# TLM_002_ESP32S3.net
KiCad netlist of a schematic drawn in Altium Designer
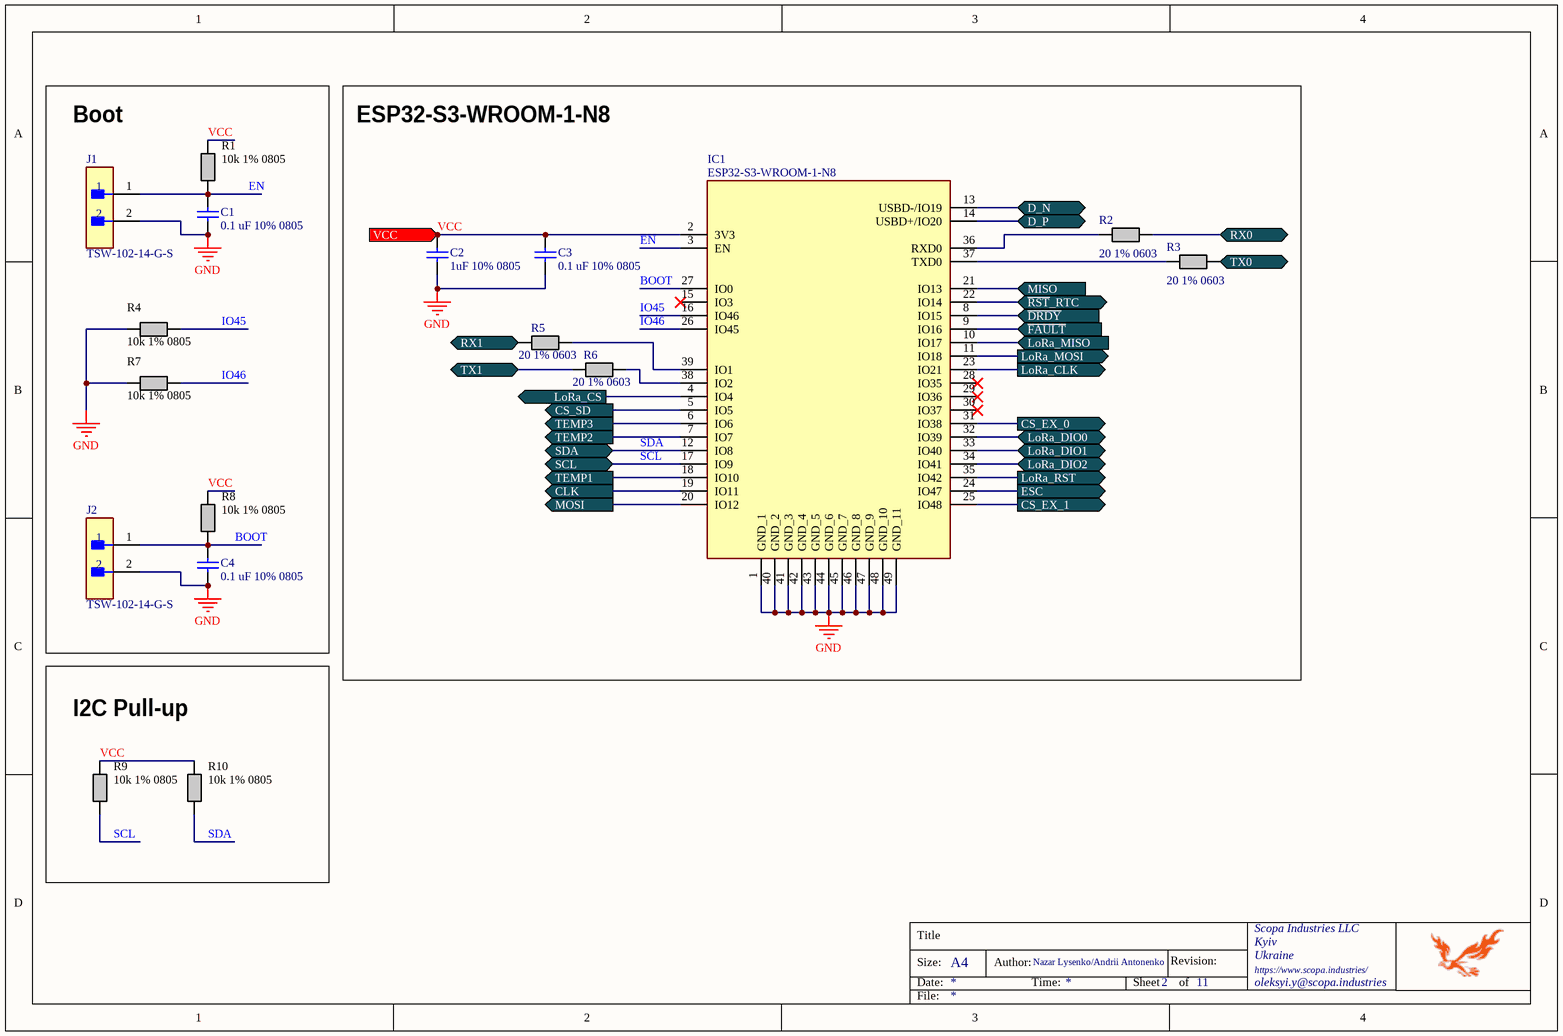
[diagram p0: TLM_002_ESP32S3.SchDoc]

(export (version "E")
  (design (tool "Eeschema 10.0.6"))
  (components
    (comp (ref "C1")
      (value "0.1 uF 10% 0805")
      (footprint "CAPC2013X140X50ML20T25")
      (fields
        (field (name "PART NUMBER") "0805DD104KAT2A")
        (field (name "MANUFACTURER") "AVX Interconnect / Elco")
      )
      (libsource (lib "Altium Content Vault") (part "CAP"))
    )
    (comp (ref "C2")
      (value "1uF 10% 0805")
      (footprint "CAPC2013X145X50NL20T20")
      (fields (field (name "PART NUMBER") "VJ0805Y105KXQRW1BC") (field (name "MANUFACTURER") "Vitramon"))
      (libsource (lib "Altium Content Vault") (part "CAP"))
    )
    (comp (ref "C3")
      (value "0.1 uF 10% 0805")
      (footprint "CAPC2013X140X50ML20T25")
      (fields
        (field (name "PART NUMBER") "0805DD104KAT2A")
        (field (name "MANUFACTURER") "AVX Interconnect / Elco")
      )
      (libsource (lib "Altium Content Vault") (part "CAP"))
    )
    (comp (ref "C4")
      (value "0.1 uF 10% 0805")
      (footprint "CAPC2013X140X50ML20T25")
      (fields
        (field (name "PART NUMBER") "0805DD104KAT2A")
        (field (name "MANUFACTURER") "AVX Interconnect / Elco")
      )
      (libsource (lib "Altium Content Vault") (part "CAP"))
    )
    (comp (ref "IC1")
      (value "ESP32-S3-WROOM-1-N8")
      (footprint "SamacSys:ESP32S3WROOM1N8R2")
      (description "Integrated Circuit")
      (fields (field (name "MOUSER PART NUMBER") "356-ESP32-S3WROOM1N8"))
      (libsource (lib "SamacSys") (part "ESP32-S3-WROOM-1-N8"))
    )
    (comp (ref "J1")
      (value "TSW-102-14-G-S")
      (footprint "FP-TSW-102-14-G-S-MFG")
      (description "CONN HEADER VERT 2POS 2.54MM")
      (libsource (lib "Altium Content Vault") (part "88c1139f9d239099ffebecbe3f7647a"))
    )
    (comp (ref "J2")
      (value "TSW-102-14-G-S")
      (footprint "FP-TSW-102-14-G-S-MFG")
      (description "CONN HEADER VERT 2POS 2.54MM")
      (libsource (lib "Altium Content Vault") (part "88c1139f9d239099ffebecbe3f7647a"))
    )
    (comp (ref "R1")
      (value "10k 1% 0805")
      (footprint "RES_0805")
      (description "Resistor 10kOhm 1% SMD 0805 Generic")
      (fields (field (name "TOLERANCE") "1%"))
      (libsource (lib "") (part "Resistor_10k_1"))
    )
    (comp (ref "R2")
      (value "20 1% 0603")
      (footprint "RES_0603")
      (description "Resistor 20Ohm 1% SMD 0603 Generic")
      (fields (field (name "TOLERANCE") "1%"))
      (libsource (lib "Generic-Schematic-Library") (part "Resistor_20"))
    )
    (comp (ref "R3")
      (value "20 1% 0603")
      (footprint "RES_0603")
      (description "Resistor 20Ohm 1% SMD 0603 Generic")
      (fields (field (name "TOLERANCE") "1%"))
      (libsource (lib "Generic-Schematic-Library") (part "Resistor_20"))
    )
    (comp (ref "R4")
      (value "10k 1% 0805")
      (footprint "RES_0805")
      (description "Resistor 10kOhm 1% SMD 0805 Generic")
      (fields (field (name "TOLERANCE") "1%"))
      (libsource (lib "Generic-Schematic-Library") (part "Resistor_10k"))
    )
    (comp (ref "R5")
      (value "20 1% 0603")
      (footprint "RES_0603")
      (description "Resistor 20Ohm 1% SMD 0603 Generic")
      (fields (field (name "TOLERANCE") "1%"))
      (libsource (lib "") (part "Resistor_20_1"))
    )
    (comp (ref "R6")
      (value "20 1% 0603")
      (footprint "RES_0603")
      (description "Resistor 20Ohm 1% SMD 0603 Generic")
      (fields (field (name "TOLERANCE") "1%"))
      (libsource (lib "") (part "Resistor_20_1"))
    )
    (comp (ref "R7")
      (value "10k 1% 0805")
      (footprint "RES_0805")
      (description "Resistor 10kOhm 1% SMD 0805 Generic")
      (fields (field (name "TOLERANCE") "1%"))
      (libsource (lib "Generic-Schematic-Library") (part "Resistor_10k"))
    )
    (comp (ref "R8")
      (value "10k 1% 0805")
      (footprint "RES_0805")
      (description "Resistor 10kOhm 1% SMD 0805 Generic")
      (fields (field (name "TOLERANCE") "1%"))
      (libsource (lib "") (part "Resistor_10k_1"))
    )
    (comp (ref "R9")
      (value "10k 1% 0805")
      (footprint "RES_0805")
      (description "Resistor 10kOhm 1% SMD 0805 Generic")
      (fields (field (name "TOLERANCE") "1%"))
      (libsource (lib "") (part "Resistor_10k_1"))
    )
    (comp (ref "R10")
      (value "10k 1% 0805")
      (footprint "RES_0805")
      (description "Resistor 10kOhm 1% SMD 0805 Generic")
      (fields (field (name "TOLERANCE") "1%"))
      (libsource (lib "") (part "Resistor_10k_1"))
    )
  )
  (nets
    (net (code "1") (name "/BOOT") (class "Default")
      (node (ref "C4") (pin "2") (pinfunction "2_2") (pintype "passive"))
      (node (ref "IC1") (pin "27") (pinfunction "IO0_27") (pintype "passive"))
      (node (ref "J2") (pin "1") (pinfunction "1_1") (pintype "passive"))
      (node (ref "R8") (pin "2") (pinfunction "2_2") (pintype "passive"))
    )
    (net (code "2") (name "/CLK") (class "Default")
      (node (ref "IC1") (pin "19") (pinfunction "IO11_19") (pintype "passive"))
    )
    (net (code "3") (name "/CS_EX_0") (class "Default")
      (node (ref "IC1") (pin "31") (pinfunction "IO38_31") (pintype "passive"))
    )
    (net (code "4") (name "/CS_EX_1") (class "Default")
      (node (ref "IC1") (pin "25") (pinfunction "IO48_25") (pintype "passive"))
    )
    (net (code "5") (name "/CS_SD") (class "Default")
      (node (ref "IC1") (pin "5") (pinfunction "IO5_5") (pintype "passive"))
    )
    (net (code "6") (name "/D_N") (class "Default")
      (node (ref "IC1") (pin "13") (pinfunction "USBD-/IO19_13") (pintype "passive"))
    )
    (net (code "7") (name "/D_P") (class "Default")
      (node (ref "IC1") (pin "14") (pinfunction "USBD+/IO20_14") (pintype "passive"))
    )
    (net (code "8") (name "/EN") (class "Default")
      (node (ref "C1") (pin "2") (pinfunction "2_2") (pintype "passive"))
      (node (ref "IC1") (pin "3") (pinfunction "EN_3") (pintype "passive"))
      (node (ref "J1") (pin "1") (pinfunction "1_1") (pintype "passive"))
      (node (ref "R1") (pin "2") (pinfunction "2_2") (pintype "passive"))
    )
    (net (code "9") (name "/ESC") (class "Default")
      (node (ref "IC1") (pin "24") (pinfunction "IO47_24") (pintype "passive"))
    )
    (net (code "10") (name "/IO45") (class "Default")
      (node (ref "IC1") (pin "16") (pinfunction "IO46_16") (pintype "passive"))
      (node (ref "R4") (pin "2") (pinfunction "2_2") (pintype "passive"))
    )
    (net (code "11") (name "/IO46") (class "Default")
      (node (ref "IC1") (pin "26") (pinfunction "IO45_26") (pintype "passive"))
      (node (ref "R7") (pin "2") (pinfunction "2_2") (pintype "passive"))
    )
    (net (code "12") (name "/LoRa_CLK") (class "Default")
      (node (ref "IC1") (pin "23") (pinfunction "IO21_23") (pintype "passive"))
    )
    (net (code "13") (name "/LoRa_CS") (class "Default")
      (node (ref "IC1") (pin "4") (pinfunction "IO4_4") (pintype "passive"))
    )
    (net (code "14") (name "/LoRa_DIO0") (class "Default")
      (node (ref "IC1") (pin "32") (pinfunction "IO39_32") (pintype "passive"))
    )
    (net (code "15") (name "/LoRa_DIO1") (class "Default")
      (node (ref "IC1") (pin "33") (pinfunction "IO40_33") (pintype "passive"))
    )
    (net (code "16") (name "/LoRa_DIO2") (class "Default")
      (node (ref "IC1") (pin "34") (pinfunction "IO41_34") (pintype "passive"))
    )
    (net (code "17") (name "/LoRa_MISO") (class "Default")
      (node (ref "IC1") (pin "10") (pinfunction "IO17_10") (pintype "passive"))
    )
    (net (code "18") (name "/LoRa_MOSI") (class "Default")
      (node (ref "IC1") (pin "11") (pinfunction "IO18_11") (pintype "passive"))
    )
    (net (code "19") (name "/LoRa_RST") (class "Default")
      (node (ref "IC1") (pin "35") (pinfunction "IO42_35") (pintype "passive"))
    )
    (net (code "20") (name "/MISO") (class "Default")
      (node (ref "IC1") (pin "21") (pinfunction "IO13_21") (pintype "passive"))
    )
    (net (code "21") (name "/MOSI") (class "Default")
      (node (ref "IC1") (pin "20") (pinfunction "IO12_20") (pintype "passive"))
    )
    (net (code "22") (name "/RX0") (class "Default")
      (node (ref "R2") (pin "2") (pinfunction "2_2") (pintype "passive"))
    )
    (net (code "23") (name "/RX1") (class "Default")
      (node (ref "R5") (pin "1") (pinfunction "1_1") (pintype "passive"))
    )
    (net (code "24") (name "/SCL") (class "Default")
      (node (ref "IC1") (pin "17") (pinfunction "IO9_17") (pintype "passive"))
      (node (ref "R9") (pin "2") (pinfunction "2_2") (pintype "passive"))
    )
    (net (code "25") (name "/SDA") (class "Default")
      (node (ref "IC1") (pin "12") (pinfunction "IO8_12") (pintype "passive"))
      (node (ref "R10") (pin "2") (pinfunction "2_2") (pintype "passive"))
    )
    (net (code "26") (name "/TEMP1") (class "Default")
      (node (ref "IC1") (pin "18") (pinfunction "IO10_18") (pintype "passive"))
    )
    (net (code "27") (name "/TEMP2") (class "Default")
      (node (ref "IC1") (pin "7") (pinfunction "IO7_7") (pintype "passive"))
    )
    (net (code "28") (name "/TEMP3") (class "Default")
      (node (ref "IC1") (pin "6") (pinfunction "IO6_6") (pintype "passive"))
    )
    (net (code "29") (name "/TX0") (class "Default")
      (node (ref "R3") (pin "2") (pinfunction "2_2") (pintype "passive"))
    )
    (net (code "30") (name "/TX1") (class "Default")
      (node (ref "R6") (pin "1") (pinfunction "1_1") (pintype "passive"))
    )
    (net (code "31") (name "/VCC") (class "Default")
      (node (ref "C2") (pin "2") (pinfunction "2_2") (pintype "passive"))
      (node (ref "C3") (pin "2") (pinfunction "2_2") (pintype "passive"))
      (node (ref "IC1") (pin "2") (pinfunction "3V3_2") (pintype "passive"))
      (node (ref "R1") (pin "1") (pinfunction "1_1") (pintype "passive"))
      (node (ref "R10") (pin "1") (pinfunction "1_1") (pintype "passive"))
      (node (ref "R8") (pin "1") (pinfunction "1_1") (pintype "passive"))
      (node (ref "R9") (pin "1") (pinfunction "1_1") (pintype "passive"))
    )
    (net (code "32") (name "/~{DRDY}") (class "Default")
      (node (ref "IC1") (pin "8") (pinfunction "IO15_8") (pintype "passive"))
    )
    (net (code "33") (name "/~{FAULT}") (class "Default")
      (node (ref "IC1") (pin "9") (pinfunction "IO16_9") (pintype "passive"))
    )
    (net (code "34") (name "/~{RST}_RTC") (class "Default")
      (node (ref "IC1") (pin "22") (pinfunction "IO14_22") (pintype "passive"))
    )
    (net (code "35") (name "GND") (class "Default")
      (node (ref "C1") (pin "1") (pinfunction "1_1") (pintype "passive"))
      (node (ref "C2") (pin "1") (pinfunction "1_1") (pintype "passive"))
      (node (ref "C3") (pin "1") (pinfunction "1_1") (pintype "passive"))
      (node (ref "C4") (pin "1") (pinfunction "1_1") (pintype "passive"))
      (node (ref "IC1") (pin "1") (pinfunction "GND_1_1") (pintype "passive"))
      (node (ref "IC1") (pin "40") (pinfunction "GND_2_40") (pintype "passive"))
      (node (ref "IC1") (pin "41") (pinfunction "GND_3_41") (pintype "passive"))
      (node (ref "IC1") (pin "42") (pinfunction "GND_4_42") (pintype "passive"))
      (node (ref "IC1") (pin "43") (pinfunction "GND_5_43") (pintype "passive"))
      (node (ref "IC1") (pin "44") (pinfunction "GND_6_44") (pintype "passive"))
      (node (ref "IC1") (pin "45") (pinfunction "GND_7_45") (pintype "passive"))
      (node (ref "IC1") (pin "46") (pinfunction "GND_8_46") (pintype "passive"))
      (node (ref "IC1") (pin "47") (pinfunction "GND_9_47") (pintype "passive"))
      (node (ref "IC1") (pin "48") (pinfunction "GND_10_48") (pintype "passive"))
      (node (ref "IC1") (pin "49") (pinfunction "GND_11_49") (pintype "passive"))
      (node (ref "J1") (pin "2") (pinfunction "2_2") (pintype "passive"))
      (node (ref "J2") (pin "2") (pinfunction "2_2") (pintype "passive"))
      (node (ref "R4") (pin "1") (pinfunction "1_1") (pintype "passive"))
      (node (ref "R7") (pin "1") (pinfunction "1_1") (pintype "passive"))
    )
    (net (code "36") (name "Net-(IC1-IO1)") (class "Default")
      (node (ref "IC1") (pin "39") (pinfunction "IO1_39") (pintype "passive"))
      (node (ref "R5") (pin "2") (pinfunction "2_2") (pintype "passive"))
    )
    (net (code "37") (name "Net-(IC1-IO2)") (class "Default")
      (node (ref "IC1") (pin "38") (pinfunction "IO2_38") (pintype "passive"))
      (node (ref "R6") (pin "2") (pinfunction "2_2") (pintype "passive"))
    )
    (net (code "38") (name "Net-(IC1-RXD0)") (class "Default")
      (node (ref "IC1") (pin "36") (pinfunction "RXD0_36") (pintype "passive"))
      (node (ref "R2") (pin "1") (pinfunction "1_1") (pintype "passive"))
    )
    (net (code "39") (name "Net-(IC1-TXD0)") (class "Default")
      (node (ref "IC1") (pin "37") (pinfunction "TXD0_37") (pintype "passive"))
      (node (ref "R3") (pin "1") (pinfunction "1_1") (pintype "passive"))
    )
    (net (code "40") (name "unconnected-(IC1-IO3-Pad15)") (class "Default")
      (node (ref "IC1") (pin "15") (pinfunction "IO3_15") (pintype "passive+no_connect"))
    )
    (net (code "41") (name "unconnected-(IC1-IO35-Pad28)") (class "Default")
      (node (ref "IC1") (pin "28") (pinfunction "IO35_28") (pintype "passive+no_connect"))
    )
    (net (code "42") (name "unconnected-(IC1-IO36-Pad29)") (class "Default")
      (node (ref "IC1") (pin "29") (pinfunction "IO36_29") (pintype "passive+no_connect"))
    )
    (net (code "43") (name "unconnected-(IC1-IO37-Pad30)") (class "Default")
      (node (ref "IC1") (pin "30") (pinfunction "IO37_30") (pintype "passive+no_connect"))
    )
  )
)
